# CATS-FAT-PM.net
KiCad netlist of a schematic drawn in Altium Designer
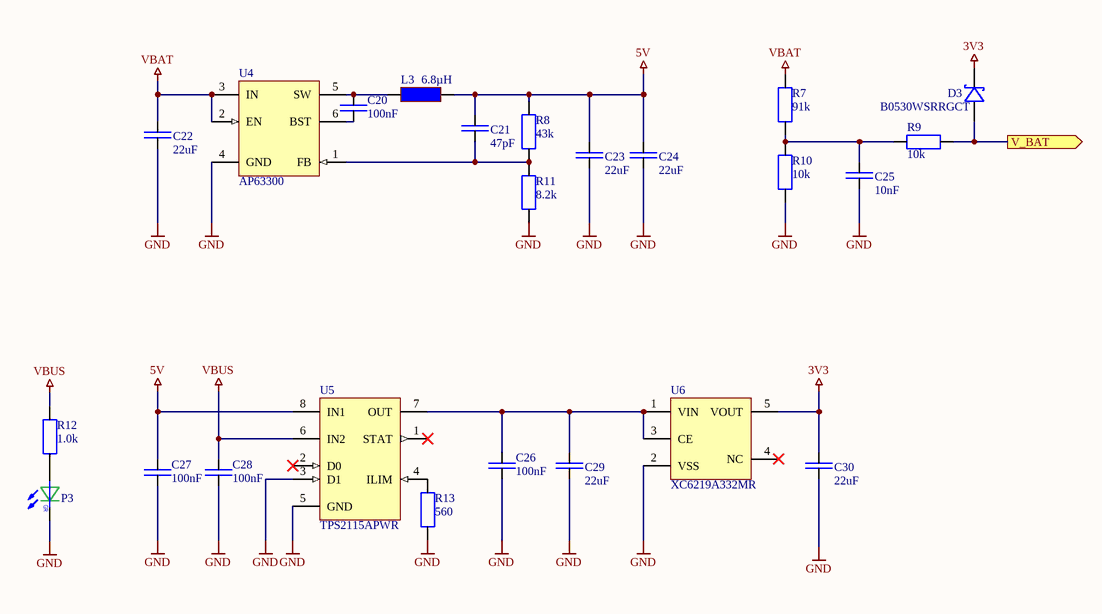
[diagram p0: CATS-FAT-PM.SchDoc]

(export (version "E")
  (design (tool "Eeschema 10.0.6"))
  (components
    (comp (ref "C20")
      (value "100nF")
      (footprint "SMD Keramikkondensator 0603")
      (description "SMD Ceramic Capacitor E6")
      (libsource (lib "Ceramic Capacitors-E6") (part "E6 - 100nF"))
    )
    (comp (ref "C21")
      (value "47pF")
      (footprint "SMD Keramikkondensator 0603")
      (description "SMD Ceramic Capacitor E6")
      (libsource (lib "Ceramic Capacitors-E6") (part "E6 - 47pF"))
    )
    (comp (ref "C22")
      (value "22uF")
      (footprint "SMD Keramikkondensator 0805")
      (description "SMD Ceramic Capacitor E6")
      (libsource (lib "Ceramic Capacitors-E6") (part "E6 - 22uF"))
    )
    (comp (ref "C23")
      (value "22uF")
      (footprint "SMD Keramikkondensator 0805")
      (description "SMD Ceramic Capacitor E6")
      (libsource (lib "Ceramic Capacitors-E6") (part "E6 - 22uF"))
    )
    (comp (ref "C24")
      (value "22uF")
      (footprint "SMD Keramikkondensator 0805")
      (description "SMD Ceramic Capacitor E6")
      (libsource (lib "Ceramic Capacitors-E6") (part "E6 - 22uF"))
    )
    (comp (ref "C25")
      (value "10nF")
      (footprint "SMD Keramikkondensator 0603")
      (description "SMD Ceramic Capacitor E6")
      (libsource (lib "Ceramic Capacitors-E6") (part "E6 - 10nF"))
    )
    (comp (ref "C26")
      (value "100nF")
      (footprint "SMD Keramikkondensator 0603")
      (description "SMD Ceramic Capacitor E6")
      (libsource (lib "Ceramic Capacitors-E6") (part "E6 - 100nF"))
    )
    (comp (ref "C27")
      (value "100nF")
      (footprint "SMD Keramikkondensator 0603")
      (description "SMD Ceramic Capacitor E6")
      (libsource (lib "Ceramic Capacitors-E6") (part "E6 - 100nF"))
    )
    (comp (ref "C28")
      (value "100nF")
      (footprint "SMD Keramikkondensator 0603")
      (description "SMD Ceramic Capacitor E6")
      (libsource (lib "Ceramic Capacitors-E6") (part "E6 - 100nF"))
    )
    (comp (ref "C29")
      (value "22uF")
      (footprint "SMD Keramikkondensator 0805")
      (description "SMD Ceramic Capacitor E6")
      (libsource (lib "Ceramic Capacitors-E6") (part "E6 - 22uF"))
    )
    (comp (ref "C30")
      (value "22uF")
      (footprint "SMD Keramikkondensator 0805")
      (description "SMD Ceramic Capacitor E6")
      (libsource (lib "Ceramic Capacitors-E6") (part "E6 - 22uF"))
    )
    (comp (ref "D3")
      (value "B0530WSRRGCT")
      (footprint "SMD Diode SOD-323F")
      (description "200mW, 0.47V Schottky Barrier Diode")
      (libsource (lib "Diodes") (part "B0530WSRRGCT"))
    )
    (comp (ref "L3")
      (value "6.8µH")
      (footprint "SMD Inductor 8x8")
      (description "FIXED IND 6.8UH 5A 25MOHM SMD")
      (libsource (lib "Inductors") (part "Inductor 6.8µH / 5A"))
    )
    (comp (ref "P3")
      (value "LED")
      (footprint "SMD LED 0603")
      (description "Color LED")
      (libsource (lib "Diodes") (part "LED"))
    )
    (comp (ref "R7")
      (value "91k")
      (footprint "SMD Widerstand 0603")
      (description "SMD Chip Resistor E24")
      (libsource (lib "Resistors-E24") (part "E24 - 91k"))
    )
    (comp (ref "R8")
      (value "43k")
      (footprint "SMD Widerstand 0603")
      (description "SMD Chip Resistor E24")
      (libsource (lib "Resistors-E24") (part "E24 - 43k"))
    )
    (comp (ref "R9")
      (value "10k")
      (footprint "SMD Widerstand 0603")
      (description "SMD Chip Resistor E24")
      (libsource (lib "") (part "E24 - 10k_1"))
    )
    (comp (ref "R10")
      (value "10k")
      (footprint "SMD Widerstand 0603")
      (description "SMD Chip Resistor E24")
      (libsource (lib "Resistors-E24") (part "E24 - 10k"))
    )
    (comp (ref "R11")
      (value "8.2k")
      (footprint "SMD Widerstand 0603")
      (description "SMD Chip Resistor E24")
      (libsource (lib "Resistors-E24") (part "E24 - 8.2k"))
    )
    (comp (ref "R12")
      (value "1.0k")
      (footprint "SMD Widerstand 0603")
      (description "SMD Chip Resistor E24")
      (libsource (lib "Resistors-E24") (part "E24 - 1.0k"))
    )
    (comp (ref "R13")
      (value "560")
      (footprint "SMD Widerstand 0603")
      (description "SMD Chip Resistor E24")
      (libsource (lib "Resistors-E24") (part "E24 - 560"))
    )
    (comp (ref "U4")
      (value "AP63300")
      (footprint "SMD IC TSOT-23-6")
      (description "3.8V TO 32V INPUT, 3A LOW IQ SYNCHRONOUS BUCK WITH ENHANCED EMI REDUCTION")
      (libsource (lib "Voltage-Converter") (part "AP63300"))
    )
    (comp (ref "U5")
      (value "TPS2115APWR")
      (footprint "SMD IC TSSOP-8")
      (description "Autoswitching Power MUX 1.25A")
      (libsource (lib "Power Management") (part "TPS2115APWR"))
    )
    (comp (ref "U6")
      (value "XC6219A332MR")
      (footprint "SMD IC SOT-23-5")
      (description "300mA High Speed LDO Regulators with ON/OFF Switch")
      (libsource (lib "Voltage-Converter") (part "XC6219A332MR"))
    )
  )
  (nets
    (net (code "1") (name "/V_BAT") (class "Default")
      (node (ref "D3") (pin "A") (pinfunction "A_A") (pintype "passive"))
      (node (ref "R9") (pin "1") (pinfunction "1_1") (pintype "passive"))
    )
    (net (code "2") (name "3V3") (class "Default")
      (node (ref "C30") (pin "2") (pinfunction "2_2") (pintype "passive"))
      (node (ref "D3") (pin "K") (pinfunction "K_K") (pintype "passive"))
      (node (ref "U6") (pin "5") (pinfunction "VOUT_5") (pintype "passive"))
    )
    (net (code "3") (name "5V") (class "Default")
      (node (ref "C21") (pin "2") (pinfunction "2_2") (pintype "passive"))
      (node (ref "C23") (pin "2") (pinfunction "2_2") (pintype "passive"))
      (node (ref "C24") (pin "2") (pinfunction "2_2") (pintype "passive"))
      (node (ref "C27") (pin "2") (pinfunction "2_2") (pintype "passive"))
      (node (ref "L3") (pin "2") (pinfunction "2_2") (pintype "passive"))
      (node (ref "R8") (pin "2") (pinfunction "2_2") (pintype "passive"))
      (node (ref "U5") (pin "8") (pinfunction "IN1_8") (pintype "passive"))
    )
    (net (code "4") (name "GND") (class "Default")
      (node (ref "C22") (pin "1") (pinfunction "1_1") (pintype "passive"))
      (node (ref "C23") (pin "1") (pinfunction "1_1") (pintype "passive"))
      (node (ref "C24") (pin "1") (pinfunction "1_1") (pintype "passive"))
      (node (ref "C25") (pin "1") (pinfunction "1_1") (pintype "passive"))
      (node (ref "C26") (pin "1") (pinfunction "1_1") (pintype "passive"))
      (node (ref "C27") (pin "1") (pinfunction "1_1") (pintype "passive"))
      (node (ref "C28") (pin "1") (pinfunction "1_1") (pintype "passive"))
      (node (ref "C29") (pin "1") (pinfunction "1_1") (pintype "passive"))
      (node (ref "C30") (pin "1") (pinfunction "1_1") (pintype "passive"))
      (node (ref "P3") (pin "K") (pinfunction "K_K") (pintype "passive"))
      (node (ref "R10") (pin "1") (pinfunction "1_1") (pintype "passive"))
      (node (ref "R11") (pin "1") (pinfunction "1_1") (pintype "passive"))
      (node (ref "R13") (pin "1") (pinfunction "1_1") (pintype "passive"))
      (node (ref "U4") (pin "4") (pinfunction "GND_4") (pintype "passive"))
      (node (ref "U5") (pin "3") (pinfunction "D1_3") (pintype "input"))
      (node (ref "U5") (pin "5") (pinfunction "GND_5") (pintype "passive"))
      (node (ref "U6") (pin "2") (pinfunction "VSS_2") (pintype "passive"))
    )
    (net (code "5") (name "Net-(C25-Pad2)") (class "Default")
      (node (ref "C25") (pin "2") (pinfunction "2_2") (pintype "passive"))
      (node (ref "R10") (pin "2") (pinfunction "2_2") (pintype "passive"))
      (node (ref "R7") (pin "1") (pinfunction "1_1") (pintype "passive"))
      (node (ref "R9") (pin "2") (pinfunction "2_2") (pintype "passive"))
    )
    (net (code "6") (name "Net-(P3-PadA)") (class "Default")
      (node (ref "P3") (pin "A") (pinfunction "A_A") (pintype "passive"))
      (node (ref "R12") (pin "1") (pinfunction "1_1") (pintype "passive"))
    )
    (net (code "7") (name "Net-(U4-BST)") (class "Default")
      (node (ref "C20") (pin "1") (pinfunction "1_1") (pintype "passive"))
      (node (ref "U4") (pin "6") (pinfunction "BST_6") (pintype "passive"))
    )
    (net (code "8") (name "Net-(U4-FB)") (class "Default")
      (node (ref "C21") (pin "1") (pinfunction "1_1") (pintype "passive"))
      (node (ref "R11") (pin "2") (pinfunction "2_2") (pintype "passive"))
      (node (ref "R8") (pin "1") (pinfunction "1_1") (pintype "passive"))
      (node (ref "U4") (pin "1") (pinfunction "FB_1") (pintype "input"))
    )
    (net (code "9") (name "Net-(U4-SW)") (class "Default")
      (node (ref "C20") (pin "2") (pinfunction "2_2") (pintype "passive"))
      (node (ref "L3") (pin "1") (pinfunction "1_1") (pintype "passive"))
      (node (ref "U4") (pin "5") (pinfunction "SW_5") (pintype "passive"))
    )
    (net (code "10") (name "Net-(U5-ILIM)") (class "Default")
      (node (ref "R13") (pin "2") (pinfunction "2_2") (pintype "passive"))
      (node (ref "U5") (pin "4") (pinfunction "ILIM_4") (pintype "input"))
    )
    (net (code "11") (name "Net-(U5-OUT)") (class "Default")
      (node (ref "C26") (pin "2") (pinfunction "2_2") (pintype "passive"))
      (node (ref "C29") (pin "2") (pinfunction "2_2") (pintype "passive"))
      (node (ref "U5") (pin "7") (pinfunction "OUT_7") (pintype "power_in"))
      (node (ref "U6") (pin "1") (pinfunction "VIN_1") (pintype "passive"))
      (node (ref "U6") (pin "3") (pinfunction "CE_3") (pintype "passive"))
    )
    (net (code "12") (name "VBAT") (class "Default")
      (node (ref "C22") (pin "2") (pinfunction "2_2") (pintype "passive"))
      (node (ref "R7") (pin "2") (pinfunction "2_2") (pintype "passive"))
      (node (ref "U4") (pin "2") (pinfunction "EN_2") (pintype "input"))
      (node (ref "U4") (pin "3") (pinfunction "IN_3") (pintype "passive"))
    )
    (net (code "13") (name "VBUS") (class "Default")
      (node (ref "C28") (pin "2") (pinfunction "2_2") (pintype "passive"))
      (node (ref "R12") (pin "2") (pinfunction "2_2") (pintype "passive"))
      (node (ref "U5") (pin "6") (pinfunction "IN2_6") (pintype "passive"))
    )
    (net (code "14") (name "unconnected-(U5-D0-Pad2)") (class "Default")
      (node (ref "U5") (pin "2") (pinfunction "D0_2") (pintype "input+no_connect"))
    )
    (net (code "15") (name "unconnected-(U5-STAT-Pad1)") (class "Default")
      (node (ref "U5") (pin "1") (pinfunction "STAT_1") (pintype "output+no_connect"))
    )
    (net (code "16") (name "unconnected-(U6-NC-Pad4)") (class "Default")
      (node (ref "U6") (pin "4") (pinfunction "NC_4") (pintype "passive+no_connect"))
    )
  )
)
